# Debugging_Board.net
KiCad netlist of a schematic drawn in EAGLE
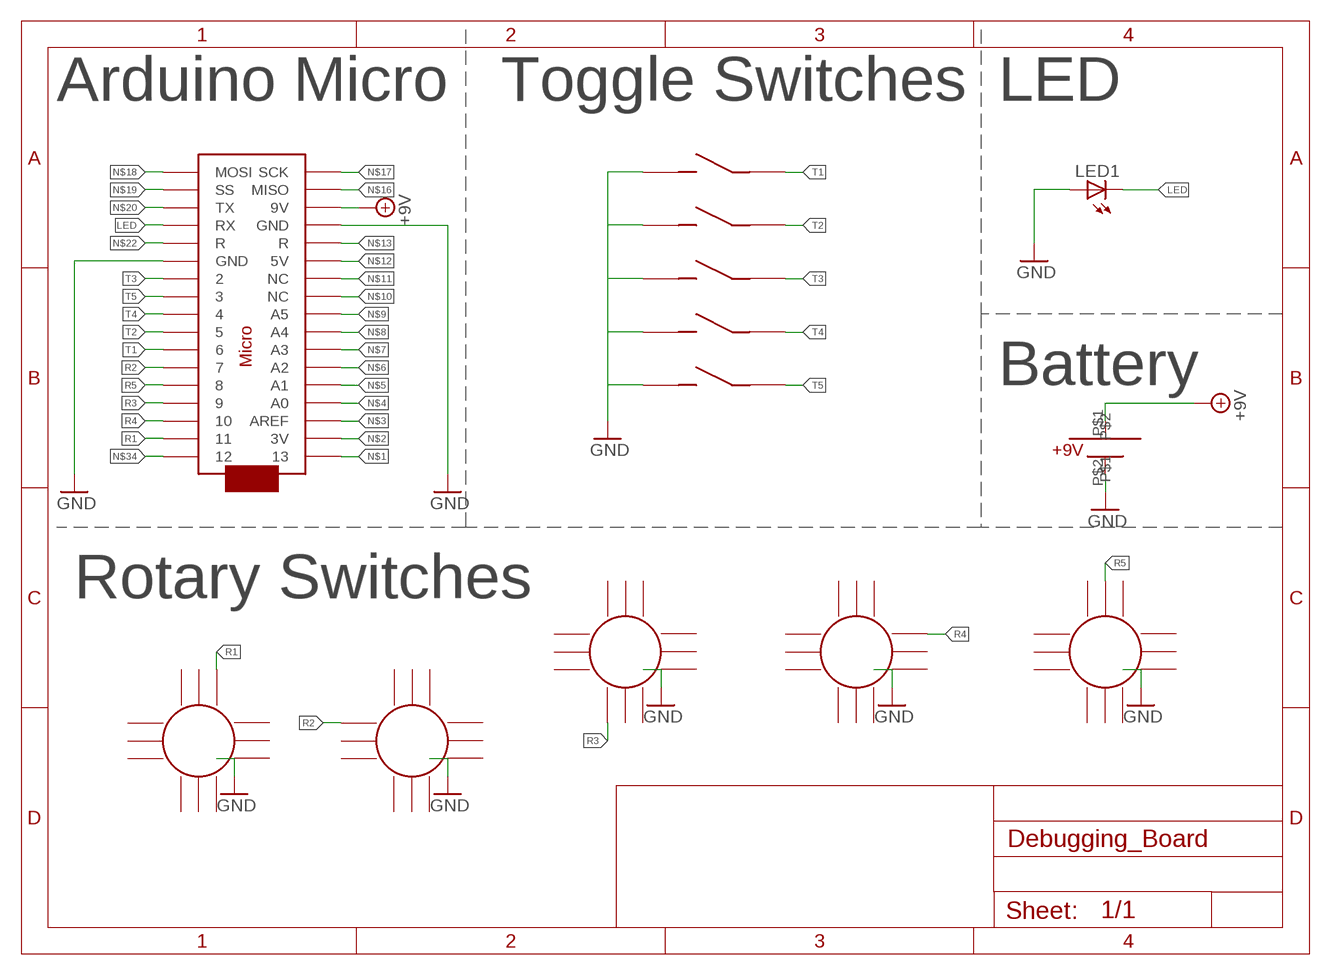
[diagram p0: schematic, sheet 1]

(export (version "E")
  (design (tool "Eeschema 10.0.6"))
  (components
    (comp (ref "LED1")
      (value "LED5MM")
      (footprint "eagle-import:LED5MM")
      (libsource (lib "eagle-import") (part "LED5MM"))
    )
    (comp (ref "U$1")
      (value "ARDUINOMICRO")
      (footprint "eagle-import:ARDUINOMICRO")
      (libsource (lib "eagle-import") (part "ARDUINOMICRO"))
    )
    (comp (ref "U$2")
      (value "TOGGLE")
      (footprint "eagle-import:SWITCH")
      (libsource (lib "eagle-import") (part "TOGGLE"))
    )
    (comp (ref "U$3")
      (value "TOGGLE")
      (footprint "eagle-import:SWITCH")
      (libsource (lib "eagle-import") (part "TOGGLE"))
    )
    (comp (ref "U$4")
      (value "TOGGLE")
      (footprint "eagle-import:SWITCH")
      (libsource (lib "eagle-import") (part "TOGGLE"))
    )
    (comp (ref "U$5")
      (value "TOGGLE")
      (footprint "eagle-import:SWITCH")
      (libsource (lib "eagle-import") (part "TOGGLE"))
    )
    (comp (ref "U$6")
      (value "TOGGLE")
      (footprint "eagle-import:SWITCH")
      (libsource (lib "eagle-import") (part "TOGGLE"))
    )
    (comp (ref "U$7")
      (value "ROTARY")
      (footprint "eagle-import:ROTARY")
      (libsource (lib "eagle-import") (part "ROTARY"))
    )
    (comp (ref "U$8")
      (value "ROTARY")
      (footprint "eagle-import:ROTARY")
      (libsource (lib "eagle-import") (part "ROTARY"))
    )
    (comp (ref "U$9")
      (value "ROTARY")
      (footprint "eagle-import:ROTARY")
      (libsource (lib "eagle-import") (part "ROTARY"))
    )
    (comp (ref "U$10")
      (value "ROTARY")
      (footprint "eagle-import:ROTARY")
      (libsource (lib "eagle-import") (part "ROTARY"))
    )
    (comp (ref "U$11")
      (value "ROTARY")
      (footprint "eagle-import:ROTARY")
      (libsource (lib "eagle-import") (part "ROTARY"))
    )
    (comp (ref "U$12")
      (value "BATTERY")
      (footprint "eagle-import:BATTERY")
      (libsource (lib "eagle-import") (part "BATTERY"))
    )
  )
  (nets
    (net (code "1") (name "+9V") (class "Default")
      (node (ref "U$1") (pin "P$20") (pinfunction "9V_P$20") (pintype "bidirectional"))
      (node (ref "U$12") (pin "P$1") (pinfunction "P$1_P$1") (pintype "bidirectional"))
    )
    (net (code "2") (name "GND") (class "Default")
      (node (ref "LED1") (pin "A") (pinfunction "A_A") (pintype "passive"))
      (node (ref "U$1") (pin "P$12") (pinfunction "GND_P$12") (pintype "bidirectional"))
      (node (ref "U$1") (pin "P$21") (pinfunction "GND_P$21") (pintype "bidirectional"))
      (node (ref "U$10") (pin "P$13") (pinfunction "P$13_P$13") (pintype "bidirectional"))
      (node (ref "U$11") (pin "P$13") (pinfunction "P$13_P$13") (pintype "bidirectional"))
      (node (ref "U$12") (pin "P$2") (pinfunction "P$2_P$2") (pintype "bidirectional"))
      (node (ref "U$2") (pin "P$1") (pinfunction "P$1_P$1") (pintype "bidirectional"))
      (node (ref "U$3") (pin "P$1") (pinfunction "P$1_P$1") (pintype "bidirectional"))
      (node (ref "U$4") (pin "P$1") (pinfunction "P$1_P$1") (pintype "bidirectional"))
      (node (ref "U$5") (pin "P$1") (pinfunction "P$1_P$1") (pintype "bidirectional"))
      (node (ref "U$6") (pin "P$1") (pinfunction "P$1_P$1") (pintype "bidirectional"))
      (node (ref "U$7") (pin "P$13") (pinfunction "P$13_P$13") (pintype "bidirectional"))
      (node (ref "U$8") (pin "P$13") (pinfunction "P$13_P$13") (pintype "bidirectional"))
      (node (ref "U$9") (pin "P$13") (pinfunction "P$13_P$13") (pintype "bidirectional"))
    )
    (net (code "3") (name "LED") (class "Default")
      (node (ref "LED1") (pin "K") (pinfunction "C_K") (pintype "passive"))
      (node (ref "U$1") (pin "P$14") (pinfunction "RX_P$14") (pintype "bidirectional"))
    )
    (net (code "4") (name "N$1") (class "Default")
      (node (ref "U$1") (pin "P$34") (pinfunction "13_P$34") (pintype "bidirectional"))
    )
    (net (code "5") (name "N$2") (class "Default")
      (node (ref "U$1") (pin "P$33") (pinfunction "3V_P$33") (pintype "bidirectional"))
    )
    (net (code "6") (name "N$3") (class "Default")
      (node (ref "U$1") (pin "P$32") (pinfunction "AREF_P$32") (pintype "bidirectional"))
    )
    (net (code "7") (name "N$4") (class "Default")
      (node (ref "U$1") (pin "P$31") (pinfunction "A0_P$31") (pintype "bidirectional"))
    )
    (net (code "8") (name "N$5") (class "Default")
      (node (ref "U$1") (pin "P$30") (pinfunction "A1_P$30") (pintype "bidirectional"))
    )
    (net (code "9") (name "N$6") (class "Default")
      (node (ref "U$1") (pin "P$29") (pinfunction "A2_P$29") (pintype "bidirectional"))
    )
    (net (code "10") (name "N$7") (class "Default")
      (node (ref "U$1") (pin "P$28") (pinfunction "A3_P$28") (pintype "bidirectional"))
    )
    (net (code "11") (name "N$8") (class "Default")
      (node (ref "U$1") (pin "P$27") (pinfunction "A4_P$27") (pintype "bidirectional"))
    )
    (net (code "12") (name "N$9") (class "Default")
      (node (ref "U$1") (pin "P$26") (pinfunction "A5_P$26") (pintype "bidirectional"))
    )
    (net (code "13") (name "N$10") (class "Default")
      (node (ref "U$1") (pin "P$25") (pinfunction "NC_P$25") (pintype "bidirectional"))
    )
    (net (code "14") (name "N$11") (class "Default")
      (node (ref "U$1") (pin "P$24") (pinfunction "NC_P$24") (pintype "bidirectional"))
    )
    (net (code "15") (name "N$12") (class "Default")
      (node (ref "U$1") (pin "P$23") (pinfunction "5V_P$23") (pintype "bidirectional"))
    )
    (net (code "16") (name "N$13") (class "Default")
      (node (ref "U$1") (pin "P$13") (pinfunction "R_P$13") (pintype "bidirectional"))
    )
    (net (code "17") (name "N$16") (class "Default")
      (node (ref "U$1") (pin "P$19") (pinfunction "MISO_P$19") (pintype "bidirectional"))
    )
    (net (code "18") (name "N$17") (class "Default")
      (node (ref "U$1") (pin "P$18") (pinfunction "SCK_P$18") (pintype "bidirectional"))
    )
    (net (code "19") (name "N$18") (class "Default")
      (node (ref "U$1") (pin "P$17") (pinfunction "MOSI_P$17") (pintype "bidirectional"))
    )
    (net (code "20") (name "N$19") (class "Default")
      (node (ref "U$1") (pin "P$16") (pinfunction "SS_P$16") (pintype "bidirectional"))
    )
    (net (code "21") (name "N$20") (class "Default")
      (node (ref "U$1") (pin "P$15") (pinfunction "TX_P$15") (pintype "bidirectional"))
    )
    (net (code "22") (name "N$22") (class "Default")
      (node (ref "U$1") (pin "P$22") (pinfunction "R_P$22") (pintype "bidirectional"))
    )
    (net (code "23") (name "N$34") (class "Default")
      (node (ref "U$1") (pin "P$1") (pinfunction "12_P$1") (pintype "bidirectional"))
    )
    (net (code "24") (name "R1") (class "Default")
      (node (ref "U$1") (pin "P$2") (pinfunction "11_P$2") (pintype "bidirectional"))
      (node (ref "U$7") (pin "P$3") (pinfunction "P$3_P$3") (pintype "bidirectional"))
    )
    (net (code "25") (name "R2") (class "Default")
      (node (ref "U$1") (pin "P$6") (pinfunction "7_P$6") (pintype "bidirectional"))
      (node (ref "U$8") (pin "P$12") (pinfunction "P$12_P$12") (pintype "bidirectional"))
    )
    (net (code "26") (name "R3") (class "Default")
      (node (ref "U$1") (pin "P$4") (pinfunction "9_P$4") (pintype "bidirectional"))
      (node (ref "U$9") (pin "P$9") (pinfunction "P$9_P$9") (pintype "bidirectional"))
    )
    (net (code "27") (name "R4") (class "Default")
      (node (ref "U$1") (pin "P$3") (pinfunction "10_P$3") (pintype "bidirectional"))
      (node (ref "U$10") (pin "P$4") (pinfunction "P$4_P$4") (pintype "bidirectional"))
    )
    (net (code "28") (name "R5") (class "Default")
      (node (ref "U$1") (pin "P$5") (pinfunction "8_P$5") (pintype "bidirectional"))
      (node (ref "U$11") (pin "P$2") (pinfunction "P$2_P$2") (pintype "bidirectional"))
    )
    (net (code "29") (name "T1") (class "Default")
      (node (ref "U$1") (pin "P$7") (pinfunction "6_P$7") (pintype "bidirectional"))
      (node (ref "U$2") (pin "P$2") (pinfunction "P$2_P$2") (pintype "bidirectional"))
    )
    (net (code "30") (name "T2") (class "Default")
      (node (ref "U$1") (pin "P$8") (pinfunction "5_P$8") (pintype "bidirectional"))
      (node (ref "U$3") (pin "P$2") (pinfunction "P$2_P$2") (pintype "bidirectional"))
    )
    (net (code "31") (name "T3") (class "Default")
      (node (ref "U$1") (pin "P$11") (pinfunction "2_P$11") (pintype "bidirectional"))
      (node (ref "U$4") (pin "P$2") (pinfunction "P$2_P$2") (pintype "bidirectional"))
    )
    (net (code "32") (name "T4") (class "Default")
      (node (ref "U$1") (pin "P$9") (pinfunction "4_P$9") (pintype "bidirectional"))
      (node (ref "U$5") (pin "P$2") (pinfunction "P$2_P$2") (pintype "bidirectional"))
    )
    (net (code "33") (name "T5") (class "Default")
      (node (ref "U$1") (pin "P$10") (pinfunction "3_P$10") (pintype "bidirectional"))
      (node (ref "U$6") (pin "P$2") (pinfunction "P$2_P$2") (pintype "bidirectional"))
    )
    (net (code "34") (name "unconnected-(U$7-PadP$1)") (class "Default")
      (node (ref "U$7") (pin "P$1") (pinfunction "P$1_P$1") (pintype "bidirectional"))
    )
    (net (code "35") (name "unconnected-(U$7-PadP$2)") (class "Default")
      (node (ref "U$7") (pin "P$2") (pinfunction "P$2_P$2") (pintype "bidirectional"))
    )
    (net (code "36") (name "unconnected-(U$7-PadP$4)") (class "Default")
      (node (ref "U$7") (pin "P$4") (pinfunction "P$4_P$4") (pintype "bidirectional"))
    )
    (net (code "37") (name "unconnected-(U$7-PadP$5)") (class "Default")
      (node (ref "U$7") (pin "P$5") (pinfunction "P$5_P$5") (pintype "bidirectional"))
    )
    (net (code "38") (name "unconnected-(U$7-PadP$6)") (class "Default")
      (node (ref "U$7") (pin "P$6") (pinfunction "P$6_P$6") (pintype "bidirectional"))
    )
    (net (code "39") (name "unconnected-(U$7-PadP$7)") (class "Default")
      (node (ref "U$7") (pin "P$7") (pinfunction "P$7_P$7") (pintype "bidirectional"))
    )
    (net (code "40") (name "unconnected-(U$7-PadP$8)") (class "Default")
      (node (ref "U$7") (pin "P$8") (pinfunction "P$8_P$8") (pintype "bidirectional"))
    )
    (net (code "41") (name "unconnected-(U$7-PadP$9)") (class "Default")
      (node (ref "U$7") (pin "P$9") (pinfunction "P$9_P$9") (pintype "bidirectional"))
    )
    (net (code "42") (name "unconnected-(U$7-PadP$10)") (class "Default")
      (node (ref "U$7") (pin "P$10") (pinfunction "P$10_P$10") (pintype "bidirectional"))
    )
    (net (code "43") (name "unconnected-(U$7-PadP$11)") (class "Default")
      (node (ref "U$7") (pin "P$11") (pinfunction "P$11_P$11") (pintype "bidirectional"))
    )
    (net (code "44") (name "unconnected-(U$7-PadP$12)") (class "Default")
      (node (ref "U$7") (pin "P$12") (pinfunction "P$12_P$12") (pintype "bidirectional"))
    )
    (net (code "45") (name "unconnected-(U$8-PadP$1)") (class "Default")
      (node (ref "U$8") (pin "P$1") (pinfunction "P$1_P$1") (pintype "bidirectional"))
    )
    (net (code "46") (name "unconnected-(U$8-PadP$2)") (class "Default")
      (node (ref "U$8") (pin "P$2") (pinfunction "P$2_P$2") (pintype "bidirectional"))
    )
    (net (code "47") (name "unconnected-(U$8-PadP$3)") (class "Default")
      (node (ref "U$8") (pin "P$3") (pinfunction "P$3_P$3") (pintype "bidirectional"))
    )
    (net (code "48") (name "unconnected-(U$8-PadP$4)") (class "Default")
      (node (ref "U$8") (pin "P$4") (pinfunction "P$4_P$4") (pintype "bidirectional"))
    )
    (net (code "49") (name "unconnected-(U$8-PadP$5)") (class "Default")
      (node (ref "U$8") (pin "P$5") (pinfunction "P$5_P$5") (pintype "bidirectional"))
    )
    (net (code "50") (name "unconnected-(U$8-PadP$6)") (class "Default")
      (node (ref "U$8") (pin "P$6") (pinfunction "P$6_P$6") (pintype "bidirectional"))
    )
    (net (code "51") (name "unconnected-(U$8-PadP$7)") (class "Default")
      (node (ref "U$8") (pin "P$7") (pinfunction "P$7_P$7") (pintype "bidirectional"))
    )
    (net (code "52") (name "unconnected-(U$8-PadP$8)") (class "Default")
      (node (ref "U$8") (pin "P$8") (pinfunction "P$8_P$8") (pintype "bidirectional"))
    )
    (net (code "53") (name "unconnected-(U$8-PadP$9)") (class "Default")
      (node (ref "U$8") (pin "P$9") (pinfunction "P$9_P$9") (pintype "bidirectional"))
    )
    (net (code "54") (name "unconnected-(U$8-PadP$10)") (class "Default")
      (node (ref "U$8") (pin "P$10") (pinfunction "P$10_P$10") (pintype "bidirectional"))
    )
    (net (code "55") (name "unconnected-(U$8-PadP$11)") (class "Default")
      (node (ref "U$8") (pin "P$11") (pinfunction "P$11_P$11") (pintype "bidirectional"))
    )
    (net (code "56") (name "unconnected-(U$9-PadP$1)") (class "Default")
      (node (ref "U$9") (pin "P$1") (pinfunction "P$1_P$1") (pintype "bidirectional"))
    )
    (net (code "57") (name "unconnected-(U$9-PadP$2)") (class "Default")
      (node (ref "U$9") (pin "P$2") (pinfunction "P$2_P$2") (pintype "bidirectional"))
    )
    (net (code "58") (name "unconnected-(U$9-PadP$3)") (class "Default")
      (node (ref "U$9") (pin "P$3") (pinfunction "P$3_P$3") (pintype "bidirectional"))
    )
    (net (code "59") (name "unconnected-(U$9-PadP$4)") (class "Default")
      (node (ref "U$9") (pin "P$4") (pinfunction "P$4_P$4") (pintype "bidirectional"))
    )
    (net (code "60") (name "unconnected-(U$9-PadP$5)") (class "Default")
      (node (ref "U$9") (pin "P$5") (pinfunction "P$5_P$5") (pintype "bidirectional"))
    )
    (net (code "61") (name "unconnected-(U$9-PadP$6)") (class "Default")
      (node (ref "U$9") (pin "P$6") (pinfunction "P$6_P$6") (pintype "bidirectional"))
    )
    (net (code "62") (name "unconnected-(U$9-PadP$7)") (class "Default")
      (node (ref "U$9") (pin "P$7") (pinfunction "P$7_P$7") (pintype "bidirectional"))
    )
    (net (code "63") (name "unconnected-(U$9-PadP$8)") (class "Default")
      (node (ref "U$9") (pin "P$8") (pinfunction "P$8_P$8") (pintype "bidirectional"))
    )
    (net (code "64") (name "unconnected-(U$9-PadP$10)") (class "Default")
      (node (ref "U$9") (pin "P$10") (pinfunction "P$10_P$10") (pintype "bidirectional"))
    )
    (net (code "65") (name "unconnected-(U$9-PadP$11)") (class "Default")
      (node (ref "U$9") (pin "P$11") (pinfunction "P$11_P$11") (pintype "bidirectional"))
    )
    (net (code "66") (name "unconnected-(U$9-PadP$12)") (class "Default")
      (node (ref "U$9") (pin "P$12") (pinfunction "P$12_P$12") (pintype "bidirectional"))
    )
    (net (code "67") (name "unconnected-(U$10-PadP$1)") (class "Default")
      (node (ref "U$10") (pin "P$1") (pinfunction "P$1_P$1") (pintype "bidirectional"))
    )
    (net (code "68") (name "unconnected-(U$10-PadP$2)") (class "Default")
      (node (ref "U$10") (pin "P$2") (pinfunction "P$2_P$2") (pintype "bidirectional"))
    )
    (net (code "69") (name "unconnected-(U$10-PadP$3)") (class "Default")
      (node (ref "U$10") (pin "P$3") (pinfunction "P$3_P$3") (pintype "bidirectional"))
    )
    (net (code "70") (name "unconnected-(U$10-PadP$5)") (class "Default")
      (node (ref "U$10") (pin "P$5") (pinfunction "P$5_P$5") (pintype "bidirectional"))
    )
    (net (code "71") (name "unconnected-(U$10-PadP$6)") (class "Default")
      (node (ref "U$10") (pin "P$6") (pinfunction "P$6_P$6") (pintype "bidirectional"))
    )
    (net (code "72") (name "unconnected-(U$10-PadP$7)") (class "Default")
      (node (ref "U$10") (pin "P$7") (pinfunction "P$7_P$7") (pintype "bidirectional"))
    )
    (net (code "73") (name "unconnected-(U$10-PadP$8)") (class "Default")
      (node (ref "U$10") (pin "P$8") (pinfunction "P$8_P$8") (pintype "bidirectional"))
    )
    (net (code "74") (name "unconnected-(U$10-PadP$9)") (class "Default")
      (node (ref "U$10") (pin "P$9") (pinfunction "P$9_P$9") (pintype "bidirectional"))
    )
    (net (code "75") (name "unconnected-(U$10-PadP$10)") (class "Default")
      (node (ref "U$10") (pin "P$10") (pinfunction "P$10_P$10") (pintype "bidirectional"))
    )
    (net (code "76") (name "unconnected-(U$10-PadP$11)") (class "Default")
      (node (ref "U$10") (pin "P$11") (pinfunction "P$11_P$11") (pintype "bidirectional"))
    )
    (net (code "77") (name "unconnected-(U$10-PadP$12)") (class "Default")
      (node (ref "U$10") (pin "P$12") (pinfunction "P$12_P$12") (pintype "bidirectional"))
    )
    (net (code "78") (name "unconnected-(U$11-PadP$1)") (class "Default")
      (node (ref "U$11") (pin "P$1") (pinfunction "P$1_P$1") (pintype "bidirectional"))
    )
    (net (code "79") (name "unconnected-(U$11-PadP$3)") (class "Default")
      (node (ref "U$11") (pin "P$3") (pinfunction "P$3_P$3") (pintype "bidirectional"))
    )
    (net (code "80") (name "unconnected-(U$11-PadP$4)") (class "Default")
      (node (ref "U$11") (pin "P$4") (pinfunction "P$4_P$4") (pintype "bidirectional"))
    )
    (net (code "81") (name "unconnected-(U$11-PadP$5)") (class "Default")
      (node (ref "U$11") (pin "P$5") (pinfunction "P$5_P$5") (pintype "bidirectional"))
    )
    (net (code "82") (name "unconnected-(U$11-PadP$6)") (class "Default")
      (node (ref "U$11") (pin "P$6") (pinfunction "P$6_P$6") (pintype "bidirectional"))
    )
    (net (code "83") (name "unconnected-(U$11-PadP$7)") (class "Default")
      (node (ref "U$11") (pin "P$7") (pinfunction "P$7_P$7") (pintype "bidirectional"))
    )
    (net (code "84") (name "unconnected-(U$11-PadP$8)") (class "Default")
      (node (ref "U$11") (pin "P$8") (pinfunction "P$8_P$8") (pintype "bidirectional"))
    )
    (net (code "85") (name "unconnected-(U$11-PadP$9)") (class "Default")
      (node (ref "U$11") (pin "P$9") (pinfunction "P$9_P$9") (pintype "bidirectional"))
    )
    (net (code "86") (name "unconnected-(U$11-PadP$10)") (class "Default")
      (node (ref "U$11") (pin "P$10") (pinfunction "P$10_P$10") (pintype "bidirectional"))
    )
    (net (code "87") (name "unconnected-(U$11-PadP$11)") (class "Default")
      (node (ref "U$11") (pin "P$11") (pinfunction "P$11_P$11") (pintype "bidirectional"))
    )
    (net (code "88") (name "unconnected-(U$11-PadP$12)") (class "Default")
      (node (ref "U$11") (pin "P$12") (pinfunction "P$12_P$12") (pintype "bidirectional"))
    )
  )
)
